# 02_GAP_JTAG_XTALs.net
KiCad netlist of a schematic drawn in Altium Designer
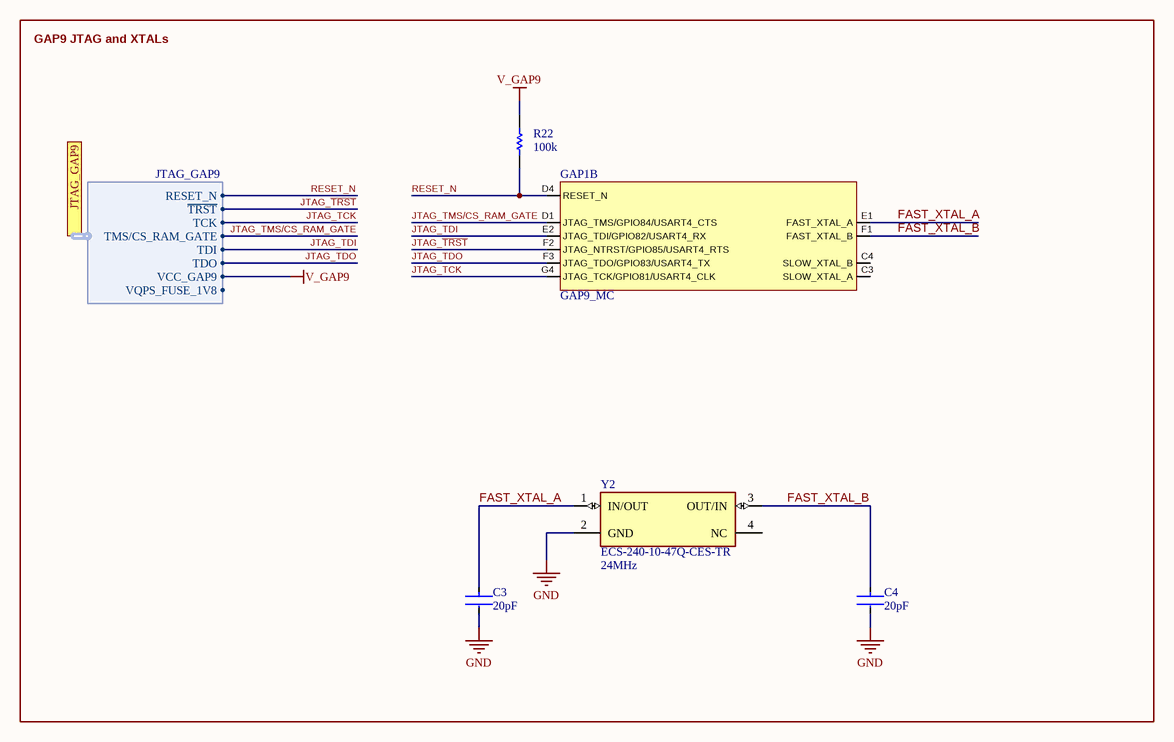
[diagram p0: 02_GAP_JTAG_XTALs.SchDoc]

(export (version "E")
  (design (tool "Eeschema 10.0.6"))
  (components
    (comp (ref "C3")
      (value "CBR02C200F5GAC")
      (footprint "EEG_PcbLib:CAPC6333_33N_KEM-L")
      (description "No Description Available")
      (fields
        (field (name "CAPACITANCE") "20pF")
        (field (name "COPYRIGHT") "Copyright (C) 2022 Ultra Librarian. All rights reserved.")
      )
      (libsource (lib "EEG_SchLib") (part "CBR02C200F5GAC"))
    )
    (comp (ref "C4")
      (value "CBR02C200F5GAC")
      (footprint "EEG_PcbLib:CAPC6333_33N_KEM-L")
      (description "No Description Available")
      (fields
        (field (name "CAPACITANCE") "20pF")
        (field (name "COPYRIGHT") "Copyright (C) 2022 Ultra Librarian. All rights reserved.")
      )
      (libsource (lib "EEG_SchLib") (part "CBR02C200F5GAC"))
    )
    (comp (ref "GAP1")
      (value "GAP9_MC")
      (footprint "EEG_PcbLib:GAP9")
      (libsource (lib "EEG_SchLib") (part "GAP9_MC"))
    )
    (comp (ref "R22")
      (value "RC0201FR-07100KL")
      (footprint "RESC0201(0603)_L")
      (description "100K 0.05W 1% 0201 (0603 Metric)  SMD")
      (fields
        (field (name "POWER") "0.05 W")
        (field (name "TOLERANCE") "1 %")
        (field (name "RESISTANCE") "100k")
      )
      (libsource (lib "Altium Content Vault") (part "RES"))
    )
    (comp (ref "Y2")
      (value "ECS-240-10-47Q-CES-TR")
      (footprint "EEG_PcbLib:XTAL_ECS-240-10-47Q-CES-TR")
      (description "24MHz Â±10ppm Crystal 10pF 150 Ohms 4-SMD, No Lead")
      (fields (field (name "MF") "ECS Inc.") (field (name "FREQUENCY") "24MHz"))
      (libsource (lib "EEG_SchLib") (part "ECS-240-10-47Q-CES-TR"))
    )
  )
  (nets
    (net (code "2") (name "/FAST_XTAL_A") (class "Default")
      (node (ref "C3") (pin "1") (pinfunction "1_1") (pintype "passive"))
      (node (ref "GAP1") (pin "E1") (pinfunction "FAST_XTAL_A_E1") (pintype "passive"))
      (node (ref "Y2") (pin "1") (pinfunction "IN/OUT_1") (pintype "bidirectional"))
    )
    (net (code "3") (name "/FAST_XTAL_B") (class "Default")
      (node (ref "C4") (pin "1") (pinfunction "1_1") (pintype "passive"))
      (node (ref "GAP1") (pin "F1") (pinfunction "FAST_XTAL_B_F1") (pintype "passive"))
      (node (ref "Y2") (pin "3") (pinfunction "OUT/IN_3") (pintype "bidirectional"))
    )
    (net (code "4") (name "/JTAG_TCK") (class "Default")
      (node (ref "GAP1") (pin "G4") (pinfunction "JTAG_TCK/GPIO81/USART4_CLK_G4") (pintype "passive"))
    )
    (net (code "5") (name "/JTAG_TDI") (class "Default")
      (node (ref "GAP1") (pin "E2") (pinfunction "JTAG_TDI/GPIO82/USART4_RX_E2") (pintype "passive"))
    )
    (net (code "6") (name "/JTAG_TDO") (class "Default")
      (node (ref "GAP1") (pin "F3") (pinfunction "JTAG_TDO/GPIO83/USART4_TX_F3") (pintype "passive"))
    )
    (net (code "7") (name "/JTAG_TMS{slash}CS_RAM_GATE") (class "Default")
      (node (ref "GAP1") (pin "D1") (pinfunction "JTAG_TMS/GPIO84/USART4_CTS_D1") (pintype "passive"))
    )
    (net (code "8") (name "/JTAG_~{TRST}") (class "Default")
      (node (ref "GAP1") (pin "F2") (pinfunction "JTAG_NTRST/GPIO85/USART4_RTS_F2") (pintype "passive"))
    )
    (net (code "9") (name "/RESET_N") (class "Default")
      (node (ref "GAP1") (pin "D4") (pinfunction "RESET_N_D4") (pintype "passive"))
      (node (ref "R22") (pin "1") (pinfunction "1_1") (pintype "passive"))
    )
    (net (code "11") (name "GND") (class "Default")
      (node (ref "C3") (pin "2") (pinfunction "2_2") (pintype "passive"))
      (node (ref "C4") (pin "2") (pinfunction "2_2") (pintype "passive"))
      (node (ref "Y2") (pin "2") (pinfunction "GND_2") (pintype "passive"))
    )
    (net (code "12") (name "V_GAP9") (class "Default")
      (node (ref "R22") (pin "2") (pinfunction "2_2") (pintype "passive"))
    )
    (net (code "13") (name "unconnected-(GAP1B-SLOW_XTAL_A-PadC3)") (class "Default")
      (node (ref "GAP1") (pin "C3") (pinfunction "SLOW_XTAL_A_C3") (pintype "passive"))
    )
    (net (code "14") (name "unconnected-(GAP1B-SLOW_XTAL_B-PadC4)") (class "Default")
      (node (ref "GAP1") (pin "C4") (pinfunction "SLOW_XTAL_B_C4") (pintype "passive"))
    )
    (net (code "15") (name "unconnected-(Y2-NC-Pad4)") (class "Default")
      (node (ref "Y2") (pin "4") (pinfunction "NC_4") (pintype "passive"))
    )
  )
)
